# motorsystem_test.net
KiCad netlist of a schematic drawn in EAGLE
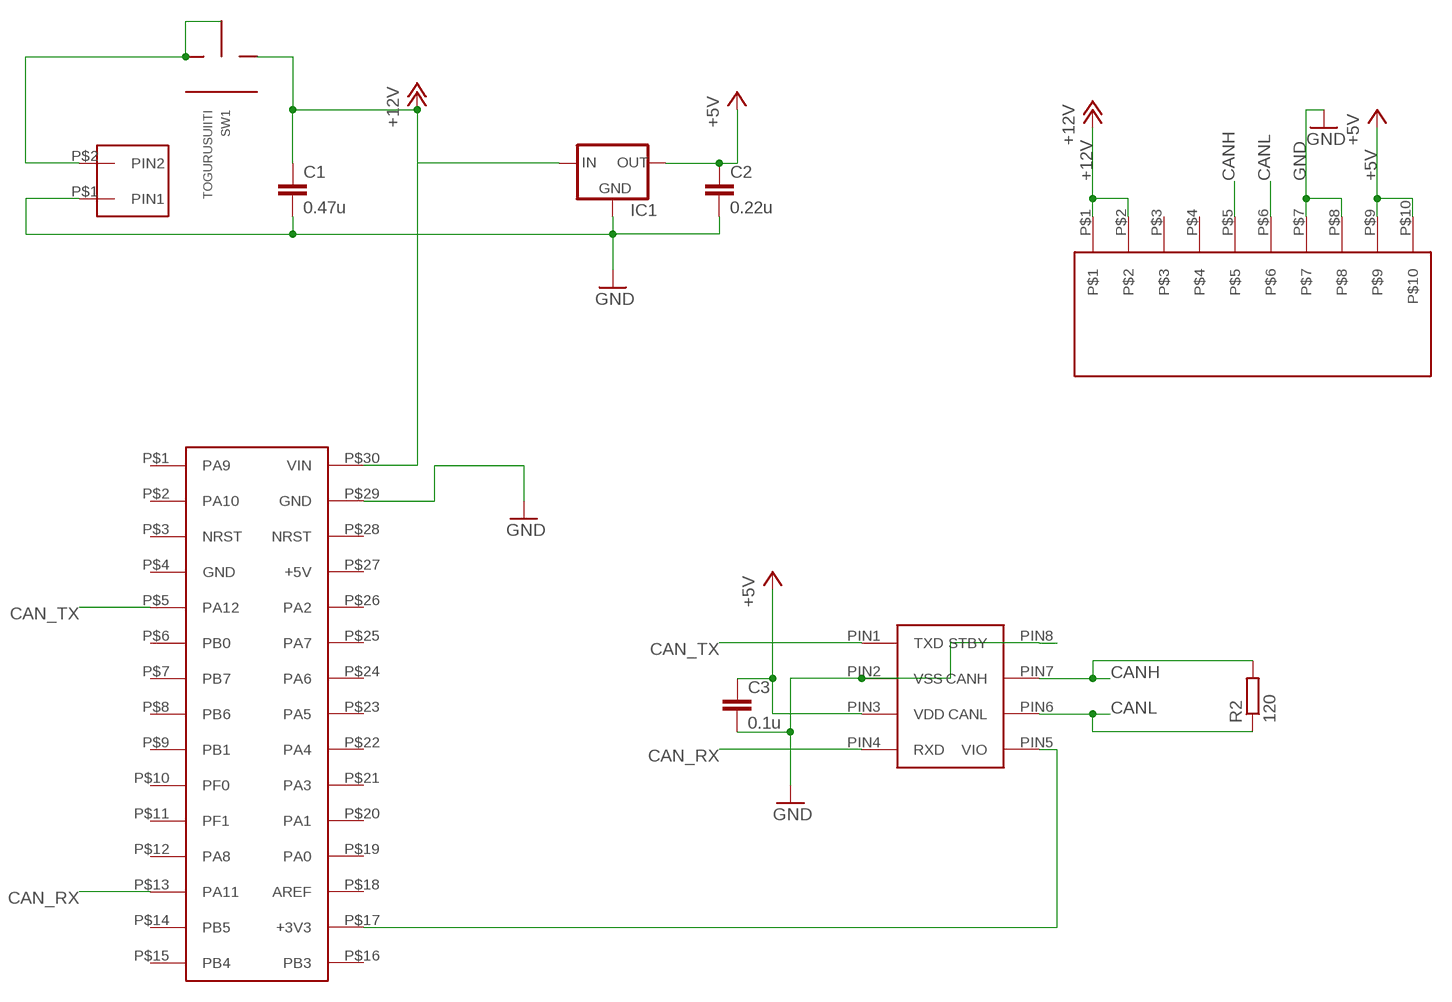
[diagram p0: schematic, sheet 1]

(export (version "E")
  (design (tool "Eeschema 10.0.6"))
  (components
    (comp (ref "C1")
      (value "0.47u")
      (footprint "eagle-import:C025-030X050")
      (libsource (lib "eagle-import") (part "C-EU025-030X050"))
    )
    (comp (ref "C2")
      (value "0.22u")
      (footprint "eagle-import:C025-030X050")
      (libsource (lib "eagle-import") (part "C-EU025-030X050"))
    )
    (comp (ref "C3")
      (value "0.1u")
      (footprint "eagle-import:C025-030X050")
      (libsource (lib "eagle-import") (part "C-EU025-030X050"))
    )
    (comp (ref "IC1")
      (value "78XXS")
      (footprint "eagle-import:78XXS")
      (libsource (lib "eagle-import") (part "78XXS"))
    )
    (comp (ref "IC2")
      (value "MCP2562")
      (footprint "eagle-import:DIL8")
      (libsource (lib "eagle-import") (part "MCP2562"))
    )
    (comp (ref "R2")
      (value "120")
      (footprint "eagle-import:0207_2V")
      (libsource (lib "eagle-import") (part "R-EU_0207/2V"))
    )
    (comp (ref "SW1")
      (value "TOGURUSUIITI")
      (footprint "eagle-import:TOGURUSUIITI")
      (libsource (lib "eagle-import") (part "TOGURUSUIITI"))
    )
    (comp (ref "U$1")
      (value "XH_2P")
      (footprint "eagle-import:XH_2P")
      (libsource (lib "eagle-import") (part "XH_2P"))
    )
    (comp (ref "U$2")
      (value "BOX10PBOX10P-L")
      (footprint "eagle-import:BOX10P-L")
      (libsource (lib "eagle-import") (part "BOX10PBOX10P-L"))
    )
    (comp (ref "U$3")
      (value "NUCLEO-F303K8")
      (footprint "eagle-import:NUCLEO-NANO")
      (libsource (lib "eagle-import") (part "NUCLEO-F303K8"))
    )
  )
  (nets
    (net (code "1") (name "+5V") (class "Default")
      (node (ref "C2") (pin "1") (pinfunction "1_1") (pintype "passive"))
      (node (ref "C3") (pin "1") (pinfunction "1_1") (pintype "passive"))
      (node (ref "IC1") (pin "OUT") (pinfunction "OUT_OUT") (pintype "passive"))
      (node (ref "IC2") (pin "PIN3") (pinfunction "VDD_PIN3") (pintype "bidirectional"))
      (node (ref "U$2") (pin "P$10") (pinfunction "P$10_P$10") (pintype "bidirectional"))
      (node (ref "U$2") (pin "P$9") (pinfunction "P$9_P$9") (pintype "bidirectional"))
    )
    (net (code "2") (name "+12V") (class "Default")
      (node (ref "C1") (pin "1") (pinfunction "1_1") (pintype "passive"))
      (node (ref "IC1") (pin "IN") (pinfunction "IN_IN") (pintype "input"))
      (node (ref "SW1") (pin "1") (pinfunction "1_1") (pintype "bidirectional"))
      (node (ref "U$2") (pin "P$1") (pinfunction "P$1_P$1") (pintype "bidirectional"))
      (node (ref "U$2") (pin "P$2") (pinfunction "P$2_P$2") (pintype "bidirectional"))
      (node (ref "U$3") (pin "P$30") (pinfunction "VIN_P$30") (pintype "bidirectional"))
    )
    (net (code "3") (name "/CANH") (class "Default")
      (node (ref "IC2") (pin "PIN7") (pinfunction "CANH_PIN7") (pintype "bidirectional"))
      (node (ref "R2") (pin "2") (pinfunction "2_2") (pintype "passive"))
      (node (ref "U$2") (pin "P$5") (pinfunction "P$5_P$5") (pintype "bidirectional"))
    )
    (net (code "4") (name "/CANL") (class "Default")
      (node (ref "IC2") (pin "PIN6") (pinfunction "CANL_PIN6") (pintype "bidirectional"))
      (node (ref "R2") (pin "1") (pinfunction "1_1") (pintype "passive"))
      (node (ref "U$2") (pin "P$6") (pinfunction "P$6_P$6") (pintype "bidirectional"))
    )
    (net (code "5") (name "/CAN_RX") (class "Default")
      (node (ref "IC2") (pin "PIN4") (pinfunction "RXD_PIN4") (pintype "bidirectional"))
      (node (ref "U$3") (pin "P$13") (pinfunction "PA11_P$13") (pintype "bidirectional"))
    )
    (net (code "6") (name "/CAN_TX") (class "Default")
      (node (ref "IC2") (pin "PIN1") (pinfunction "TXD_PIN1") (pintype "bidirectional"))
      (node (ref "U$3") (pin "P$5") (pinfunction "PA12_P$5") (pintype "bidirectional"))
    )
    (net (code "7") (name "GND") (class "Default")
      (node (ref "C1") (pin "2") (pinfunction "2_2") (pintype "passive"))
      (node (ref "C2") (pin "2") (pinfunction "2_2") (pintype "passive"))
      (node (ref "C3") (pin "2") (pinfunction "2_2") (pintype "passive"))
      (node (ref "IC1") (pin "GND") (pinfunction "GND_GND") (pintype "input"))
      (node (ref "IC2") (pin "PIN2") (pinfunction "VSS_PIN2") (pintype "bidirectional"))
      (node (ref "IC2") (pin "PIN8") (pinfunction "STBY_PIN8") (pintype "bidirectional"))
      (node (ref "U$1") (pin "P$1") (pinfunction "PIN1_P$1") (pintype "bidirectional"))
      (node (ref "U$2") (pin "P$7") (pinfunction "P$7_P$7") (pintype "bidirectional"))
      (node (ref "U$2") (pin "P$8") (pinfunction "P$8_P$8") (pintype "bidirectional"))
      (node (ref "U$3") (pin "P$29") (pinfunction "GND_P$29") (pintype "bidirectional"))
    )
    (net (code "8") (name "Net-(IC2-VIO)") (class "Default")
      (node (ref "IC2") (pin "PIN5") (pinfunction "VIO_PIN5") (pintype "bidirectional"))
      (node (ref "U$3") (pin "P$17") (pinfunction "+3V3_P$17") (pintype "bidirectional"))
    )
    (net (code "9") (name "Net-(U$1-PIN2)") (class "Default")
      (node (ref "SW1") (pin "2") (pinfunction "2_2") (pintype "bidirectional"))
      (node (ref "SW1") (pin "C") (pinfunction "C_C") (pintype "bidirectional"))
      (node (ref "U$1") (pin "P$2") (pinfunction "PIN2_P$2") (pintype "bidirectional"))
    )
    (net (code "10") (name "unconnected-(SW1-NC-PadNC@2)") (class "Default")
      (node (ref "SW1") (pin "NC@2") (pinfunction "NC_NC@2") (pintype "bidirectional"))
    )
    (net (code "11") (name "unconnected-(SW1-PadNC)") (class "Default")
      (node (ref "SW1") (pin "NC") (pinfunction "NC_NC") (pintype "bidirectional"))
    )
    (net (code "12") (name "unconnected-(U$2-PadP$3)") (class "Default")
      (node (ref "U$2") (pin "P$3") (pinfunction "P$3_P$3") (pintype "bidirectional"))
    )
    (net (code "13") (name "unconnected-(U$2-PadP$4)") (class "Default")
      (node (ref "U$2") (pin "P$4") (pinfunction "P$4_P$4") (pintype "bidirectional"))
    )
    (net (code "14") (name "unconnected-(U$3-+5V-PadP$27)") (class "Default")
      (node (ref "U$3") (pin "P$27") (pinfunction "+5V_P$27") (pintype "bidirectional"))
    )
    (net (code "15") (name "unconnected-(U$3-AREF-PadP$18)") (class "Default")
      (node (ref "U$3") (pin "P$18") (pinfunction "AREF_P$18") (pintype "bidirectional"))
    )
    (net (code "16") (name "unconnected-(U$3-GND-PadP$4)") (class "Default")
      (node (ref "U$3") (pin "P$4") (pinfunction "GND_P$4") (pintype "bidirectional"))
    )
    (net (code "17") (name "unconnected-(U$3-NRST-PadP$3)") (class "Default")
      (node (ref "U$3") (pin "P$3") (pinfunction "NRST_P$3") (pintype "bidirectional"))
    )
    (net (code "18") (name "unconnected-(U$3-NRST-PadP$28)") (class "Default")
      (node (ref "U$3") (pin "P$28") (pinfunction "NRST_P$28") (pintype "bidirectional"))
    )
    (net (code "19") (name "unconnected-(U$3-PA0-PadP$19)") (class "Default")
      (node (ref "U$3") (pin "P$19") (pinfunction "PA0_P$19") (pintype "bidirectional"))
    )
    (net (code "20") (name "unconnected-(U$3-PA1-PadP$20)") (class "Default")
      (node (ref "U$3") (pin "P$20") (pinfunction "PA1_P$20") (pintype "bidirectional"))
    )
    (net (code "21") (name "unconnected-(U$3-PA2-PadP$26)") (class "Default")
      (node (ref "U$3") (pin "P$26") (pinfunction "PA2_P$26") (pintype "bidirectional"))
    )
    (net (code "22") (name "unconnected-(U$3-PA3-PadP$21)") (class "Default")
      (node (ref "U$3") (pin "P$21") (pinfunction "PA3_P$21") (pintype "bidirectional"))
    )
    (net (code "23") (name "unconnected-(U$3-PA4-PadP$22)") (class "Default")
      (node (ref "U$3") (pin "P$22") (pinfunction "PA4_P$22") (pintype "bidirectional"))
    )
    (net (code "24") (name "unconnected-(U$3-PA5-PadP$23)") (class "Default")
      (node (ref "U$3") (pin "P$23") (pinfunction "PA5_P$23") (pintype "bidirectional"))
    )
    (net (code "25") (name "unconnected-(U$3-PA6-PadP$24)") (class "Default")
      (node (ref "U$3") (pin "P$24") (pinfunction "PA6_P$24") (pintype "bidirectional"))
    )
    (net (code "26") (name "unconnected-(U$3-PA7-PadP$25)") (class "Default")
      (node (ref "U$3") (pin "P$25") (pinfunction "PA7_P$25") (pintype "bidirectional"))
    )
    (net (code "27") (name "unconnected-(U$3-PA8-PadP$12)") (class "Default")
      (node (ref "U$3") (pin "P$12") (pinfunction "PA8_P$12") (pintype "bidirectional"))
    )
    (net (code "28") (name "unconnected-(U$3-PA9-PadP$1)") (class "Default")
      (node (ref "U$3") (pin "P$1") (pinfunction "PA9_P$1") (pintype "bidirectional"))
    )
    (net (code "29") (name "unconnected-(U$3-PA10-PadP$2)") (class "Default")
      (node (ref "U$3") (pin "P$2") (pinfunction "PA10_P$2") (pintype "bidirectional"))
    )
    (net (code "30") (name "unconnected-(U$3-PB0-PadP$6)") (class "Default")
      (node (ref "U$3") (pin "P$6") (pinfunction "PB0_P$6") (pintype "bidirectional"))
    )
    (net (code "31") (name "unconnected-(U$3-PB1-PadP$9)") (class "Default")
      (node (ref "U$3") (pin "P$9") (pinfunction "PB1_P$9") (pintype "bidirectional"))
    )
    (net (code "32") (name "unconnected-(U$3-PB3-PadP$16)") (class "Default")
      (node (ref "U$3") (pin "P$16") (pinfunction "PB3_P$16") (pintype "bidirectional"))
    )
    (net (code "33") (name "unconnected-(U$3-PB4-PadP$15)") (class "Default")
      (node (ref "U$3") (pin "P$15") (pinfunction "PB4_P$15") (pintype "bidirectional"))
    )
    (net (code "34") (name "unconnected-(U$3-PB5-PadP$14)") (class "Default")
      (node (ref "U$3") (pin "P$14") (pinfunction "PB5_P$14") (pintype "bidirectional"))
    )
    (net (code "35") (name "unconnected-(U$3-PB6-PadP$8)") (class "Default")
      (node (ref "U$3") (pin "P$8") (pinfunction "PB6_P$8") (pintype "bidirectional"))
    )
    (net (code "36") (name "unconnected-(U$3-PB7-PadP$7)") (class "Default")
      (node (ref "U$3") (pin "P$7") (pinfunction "PB7_P$7") (pintype "bidirectional"))
    )
    (net (code "37") (name "unconnected-(U$3-PF0-PadP$10)") (class "Default")
      (node (ref "U$3") (pin "P$10") (pinfunction "PF0_P$10") (pintype "bidirectional"))
    )
    (net (code "38") (name "unconnected-(U$3-PF1-PadP$11)") (class "Default")
      (node (ref "U$3") (pin "P$11") (pinfunction "PF1_P$11") (pintype "bidirectional"))
    )
  )
)
